# NeoPixelVU.net
KiCad netlist of a schematic drawn in EAGLE
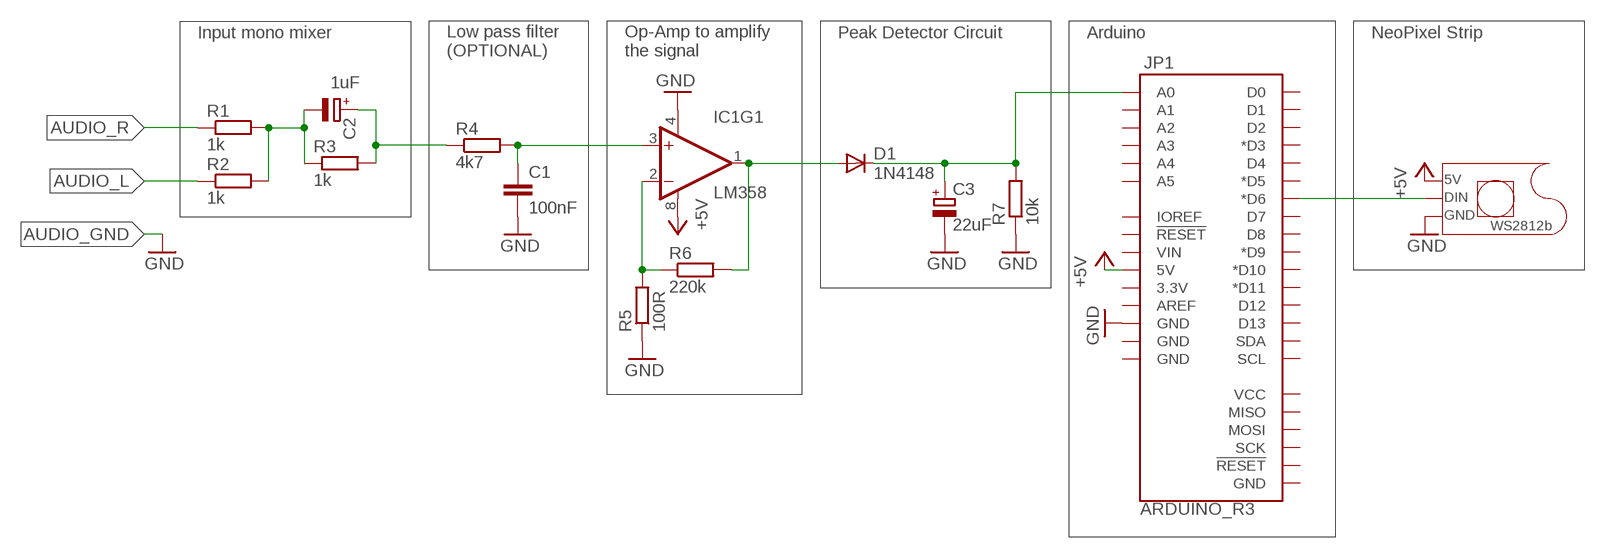
[diagram p0: schematic, sheet 1]

(export (version "E")
  (design (tool "Eeschema 10.0.6"))
  (components
    (comp (ref "C1")
      (value "100nF")
      (footprint "eagle-import:C025-024X044")
      (libsource (lib "eagle-import") (part "C-EU025-024X044"))
    )
    (comp (ref "C2")
      (value "1uF")
      (footprint "eagle-import:085CS_1AR")
      (libsource (lib "eagle-import") (part "CPOL-EU085CS-1AR"))
    )
    (comp (ref "C3")
      (value "22uF")
      (footprint "eagle-import:085CS_1AR")
      (libsource (lib "eagle-import") (part "CPOL-EU085CS-1AR"))
    )
    (comp (ref "D1")
      (value "1N4148")
      (footprint "eagle-import:DO35-10")
      (libsource (lib "eagle-import") (part "1N4148DO35-10"))
    )
    (comp (ref "IC1")
      (value "LM358")
      (footprint "eagle-import:DIP08")
      (libsource (lib "eagle-import") (part "LM358"))
    )
    (comp (ref "JP1")
      (value "ARDUINO_R3")
      (footprint "eagle-import:ARDUINO_R3")
      (libsource (lib "eagle-import") (part "ARDUINO_R3"))
    )
    (comp (ref "R1")
      (value "1k")
      (footprint "eagle-import:0411V")
      (libsource (lib "eagle-import") (part "R-EU_0411/3V"))
    )
    (comp (ref "R2")
      (value "1k")
      (footprint "eagle-import:0411V")
      (libsource (lib "eagle-import") (part "R-EU_0411/3V"))
    )
    (comp (ref "R3")
      (value "1k")
      (footprint "eagle-import:0411V")
      (libsource (lib "eagle-import") (part "R-EU_0411/3V"))
    )
    (comp (ref "R4")
      (value "4k7")
      (footprint "eagle-import:0411V")
      (libsource (lib "eagle-import") (part "R-EU_0411/3V"))
    )
    (comp (ref "R5")
      (value "100R")
      (footprint "eagle-import:0411V")
      (libsource (lib "eagle-import") (part "R-EU_0411/3V"))
    )
    (comp (ref "R6")
      (value "220k")
      (footprint "eagle-import:0411V")
      (libsource (lib "eagle-import") (part "R-EU_0411/3V"))
    )
    (comp (ref "R7")
      (value "10k")
      (footprint "eagle-import:0411V")
      (libsource (lib "eagle-import") (part "R-EU_0411/3V"))
    )
  )
  (nets
    (net (code "1") (name "+5V") (class "Default")
      (node (ref "IC1") (pin "8") (pinfunction "V+_8") (pintype "power_in"))
      (node (ref "JP1") (pin "5V") (pinfunction "5V_5V") (pintype "bidirectional"))
    )
    (net (code "2") (name "AUDIO_GND") (class "Default")
      (node (ref "C1") (pin "2") (pinfunction "2_2") (pintype "passive"))
      (node (ref "C3") (pin "-") (pinfunction "-_-") (pintype "passive"))
      (node (ref "IC1") (pin "4") (pinfunction "V-_4") (pintype "power_in"))
      (node (ref "JP1") (pin "GND@4") (pinfunction "GND_GND@4") (pintype "bidirectional"))
      (node (ref "R5") (pin "1") (pinfunction "1_1") (pintype "passive"))
      (node (ref "R7") (pin "1") (pinfunction "1_1") (pintype "passive"))
    )
    (net (code "3") (name "AUDIO_L") (class "Default")
      (node (ref "R2") (pin "1") (pinfunction "1_1") (pintype "passive"))
    )
    (net (code "4") (name "AUDIO_R") (class "Default")
      (node (ref "R1") (pin "1") (pinfunction "1_1") (pintype "passive"))
    )
    (net (code "5") (name "Net-(C2-Pad+)") (class "Default")
      (node (ref "C2") (pin "+") (pinfunction "+_+") (pintype "passive"))
      (node (ref "R3") (pin "2") (pinfunction "2_2") (pintype "passive"))
      (node (ref "R4") (pin "1") (pinfunction "1_1") (pintype "passive"))
    )
    (net (code "6") (name "Net-(C2-Pad-)") (class "Default")
      (node (ref "C2") (pin "-") (pinfunction "-_-") (pintype "passive"))
      (node (ref "R1") (pin "2") (pinfunction "2_2") (pintype "passive"))
      (node (ref "R2") (pin "2") (pinfunction "2_2") (pintype "passive"))
      (node (ref "R3") (pin "1") (pinfunction "1_1") (pintype "passive"))
    )
    (net (code "7") (name "Net-(C3-Pad+)") (class "Default")
      (node (ref "C3") (pin "+") (pinfunction "+_+") (pintype "passive"))
      (node (ref "D1") (pin "C") (pinfunction "C_C") (pintype "passive"))
      (node (ref "JP1") (pin "A0") (pinfunction "A0_A0") (pintype "bidirectional"))
      (node (ref "R7") (pin "2") (pinfunction "2_2") (pintype "passive"))
    )
    (net (code "8") (name "Net-(IC1A-+IN)") (class "Default")
      (node (ref "C1") (pin "1") (pinfunction "1_1") (pintype "passive"))
      (node (ref "IC1") (pin "3") (pinfunction "+IN_3") (pintype "input"))
      (node (ref "R4") (pin "2") (pinfunction "2_2") (pintype "passive"))
    )
    (net (code "9") (name "Net-(IC1A--IN)") (class "Default")
      (node (ref "IC1") (pin "2") (pinfunction "-IN_2") (pintype "input"))
      (node (ref "R5") (pin "2") (pinfunction "2_2") (pintype "passive"))
      (node (ref "R6") (pin "1") (pinfunction "1_1") (pintype "passive"))
    )
    (net (code "10") (name "Net-(IC1A-OUT)") (class "Default")
      (node (ref "D1") (pin "A") (pinfunction "A_A") (pintype "passive"))
      (node (ref "IC1") (pin "1") (pinfunction "OUT_1") (pintype "output"))
      (node (ref "R6") (pin "2") (pinfunction "2_2") (pintype "passive"))
    )
    (net (code "11") (name "unconnected-(JP1-*D3-PadD3)") (class "Default")
      (node (ref "JP1") (pin "D3") (pinfunction "*D3_D3") (pintype "bidirectional"))
    )
    (net (code "12") (name "unconnected-(JP1-*D5-PadD5)") (class "Default")
      (node (ref "JP1") (pin "D5") (pinfunction "*D5_D5") (pintype "bidirectional"))
    )
    (net (code "13") (name "unconnected-(JP1-*D6-PadD6)") (class "Default")
      (node (ref "JP1") (pin "D6") (pinfunction "*D6_D6") (pintype "bidirectional"))
    )
    (net (code "14") (name "unconnected-(JP1-*D9-PadD9)") (class "Default")
      (node (ref "JP1") (pin "D9") (pinfunction "*D9_D9") (pintype "bidirectional"))
    )
    (net (code "15") (name "unconnected-(JP1-*D10-PadD10)") (class "Default")
      (node (ref "JP1") (pin "D10") (pinfunction "*D10_D10") (pintype "bidirectional"))
    )
    (net (code "16") (name "unconnected-(JP1-*D11-PadD11)") (class "Default")
      (node (ref "JP1") (pin "D11") (pinfunction "*D11_D11") (pintype "bidirectional"))
    )
    (net (code "17") (name "unconnected-(JP1-GND-PadGND@1)") (class "Default")
      (node (ref "JP1") (pin "GND@1") (pinfunction "GND_GND@1") (pintype "bidirectional"))
    )
    (net (code "18") (name "unconnected-(JP1-GND-PadGND@2)") (class "Default")
      (node (ref "JP1") (pin "GND@2") (pinfunction "GND_GND@2") (pintype "bidirectional"))
    )
    (net (code "19") (name "unconnected-(JP1-GND-PadGND@3)") (class "Default")
      (node (ref "JP1") (pin "GND@3") (pinfunction "GND_GND@3") (pintype "bidirectional"))
    )
    (net (code "20") (name "unconnected-(JP1-Pad3.3V)") (class "Default")
      (node (ref "JP1") (pin "3.3V") (pinfunction "3.3V_3.3V") (pintype "bidirectional"))
    )
    (net (code "21") (name "unconnected-(JP1-PadA1)") (class "Default")
      (node (ref "JP1") (pin "A1") (pinfunction "A1_A1") (pintype "bidirectional"))
    )
    (net (code "22") (name "unconnected-(JP1-PadA2)") (class "Default")
      (node (ref "JP1") (pin "A2") (pinfunction "A2_A2") (pintype "bidirectional"))
    )
    (net (code "23") (name "unconnected-(JP1-PadA3)") (class "Default")
      (node (ref "JP1") (pin "A3") (pinfunction "A3_A3") (pintype "bidirectional"))
    )
    (net (code "24") (name "unconnected-(JP1-PadA4)") (class "Default")
      (node (ref "JP1") (pin "A4") (pinfunction "A4_A4") (pintype "bidirectional"))
    )
    (net (code "25") (name "unconnected-(JP1-PadA5)") (class "Default")
      (node (ref "JP1") (pin "A5") (pinfunction "A5_A5") (pintype "bidirectional"))
    )
    (net (code "26") (name "unconnected-(JP1-PadAREF)") (class "Default")
      (node (ref "JP1") (pin "AREF") (pinfunction "AREF_AREF") (pintype "bidirectional"))
    )
    (net (code "27") (name "unconnected-(JP1-PadD0)") (class "Default")
      (node (ref "JP1") (pin "D0") (pinfunction "D0_D0") (pintype "bidirectional"))
    )
    (net (code "28") (name "unconnected-(JP1-PadD1)") (class "Default")
      (node (ref "JP1") (pin "D1") (pinfunction "D1_D1") (pintype "bidirectional"))
    )
    (net (code "29") (name "unconnected-(JP1-PadD2)") (class "Default")
      (node (ref "JP1") (pin "D2") (pinfunction "D2_D2") (pintype "bidirectional"))
    )
    (net (code "30") (name "unconnected-(JP1-PadD4)") (class "Default")
      (node (ref "JP1") (pin "D4") (pinfunction "D4_D4") (pintype "bidirectional"))
    )
    (net (code "31") (name "unconnected-(JP1-PadD7)") (class "Default")
      (node (ref "JP1") (pin "D7") (pinfunction "D7_D7") (pintype "bidirectional"))
    )
    (net (code "32") (name "unconnected-(JP1-PadD8)") (class "Default")
      (node (ref "JP1") (pin "D8") (pinfunction "D8_D8") (pintype "bidirectional"))
    )
    (net (code "33") (name "unconnected-(JP1-PadD12)") (class "Default")
      (node (ref "JP1") (pin "D12") (pinfunction "D12_D12") (pintype "bidirectional"))
    )
    (net (code "34") (name "unconnected-(JP1-PadD13)") (class "Default")
      (node (ref "JP1") (pin "D13") (pinfunction "D13_D13") (pintype "bidirectional"))
    )
    (net (code "35") (name "unconnected-(JP1-PadIOREF)") (class "Default")
      (node (ref "JP1") (pin "IOREF") (pinfunction "IOREF_IOREF") (pintype "bidirectional"))
    )
    (net (code "36") (name "unconnected-(JP1-PadMISO)") (class "Default")
      (node (ref "JP1") (pin "MISO") (pinfunction "MISO_MISO") (pintype "bidirectional"))
    )
    (net (code "37") (name "unconnected-(JP1-PadMOSI)") (class "Default")
      (node (ref "JP1") (pin "MOSI") (pinfunction "MOSI_MOSI") (pintype "bidirectional"))
    )
    (net (code "38") (name "unconnected-(JP1-PadSCK)") (class "Default")
      (node (ref "JP1") (pin "SCK") (pinfunction "SCK_SCK") (pintype "bidirectional"))
    )
    (net (code "39") (name "unconnected-(JP1-PadSCL)") (class "Default")
      (node (ref "JP1") (pin "SCL") (pinfunction "SCL_SCL") (pintype "bidirectional"))
    )
    (net (code "40") (name "unconnected-(JP1-PadSDA)") (class "Default")
      (node (ref "JP1") (pin "SDA") (pinfunction "SDA_SDA") (pintype "bidirectional"))
    )
    (net (code "41") (name "unconnected-(JP1-PadVCC)") (class "Default")
      (node (ref "JP1") (pin "VCC") (pinfunction "VCC_VCC") (pintype "bidirectional"))
    )
    (net (code "42") (name "unconnected-(JP1-PadVIN)") (class "Default")
      (node (ref "JP1") (pin "VIN") (pinfunction "VIN_VIN") (pintype "bidirectional"))
    )
    (net (code "43") (name "unconnected-(JP1-~{RESET}-PadRESET@1)") (class "Default")
      (node (ref "JP1") (pin "RESET@1") (pinfunction "~{RESET}_RESET@1") (pintype "bidirectional"))
    )
    (net (code "44") (name "unconnected-(JP1-~{RESET}-PadRESET@2)") (class "Default")
      (node (ref "JP1") (pin "RESET@2") (pinfunction "~{RESET}_RESET@2") (pintype "bidirectional"))
    )
  )
)
